# RADG-GPSRF-S02-V00.net
KiCad netlist of a schematic drawn in Altium Designer
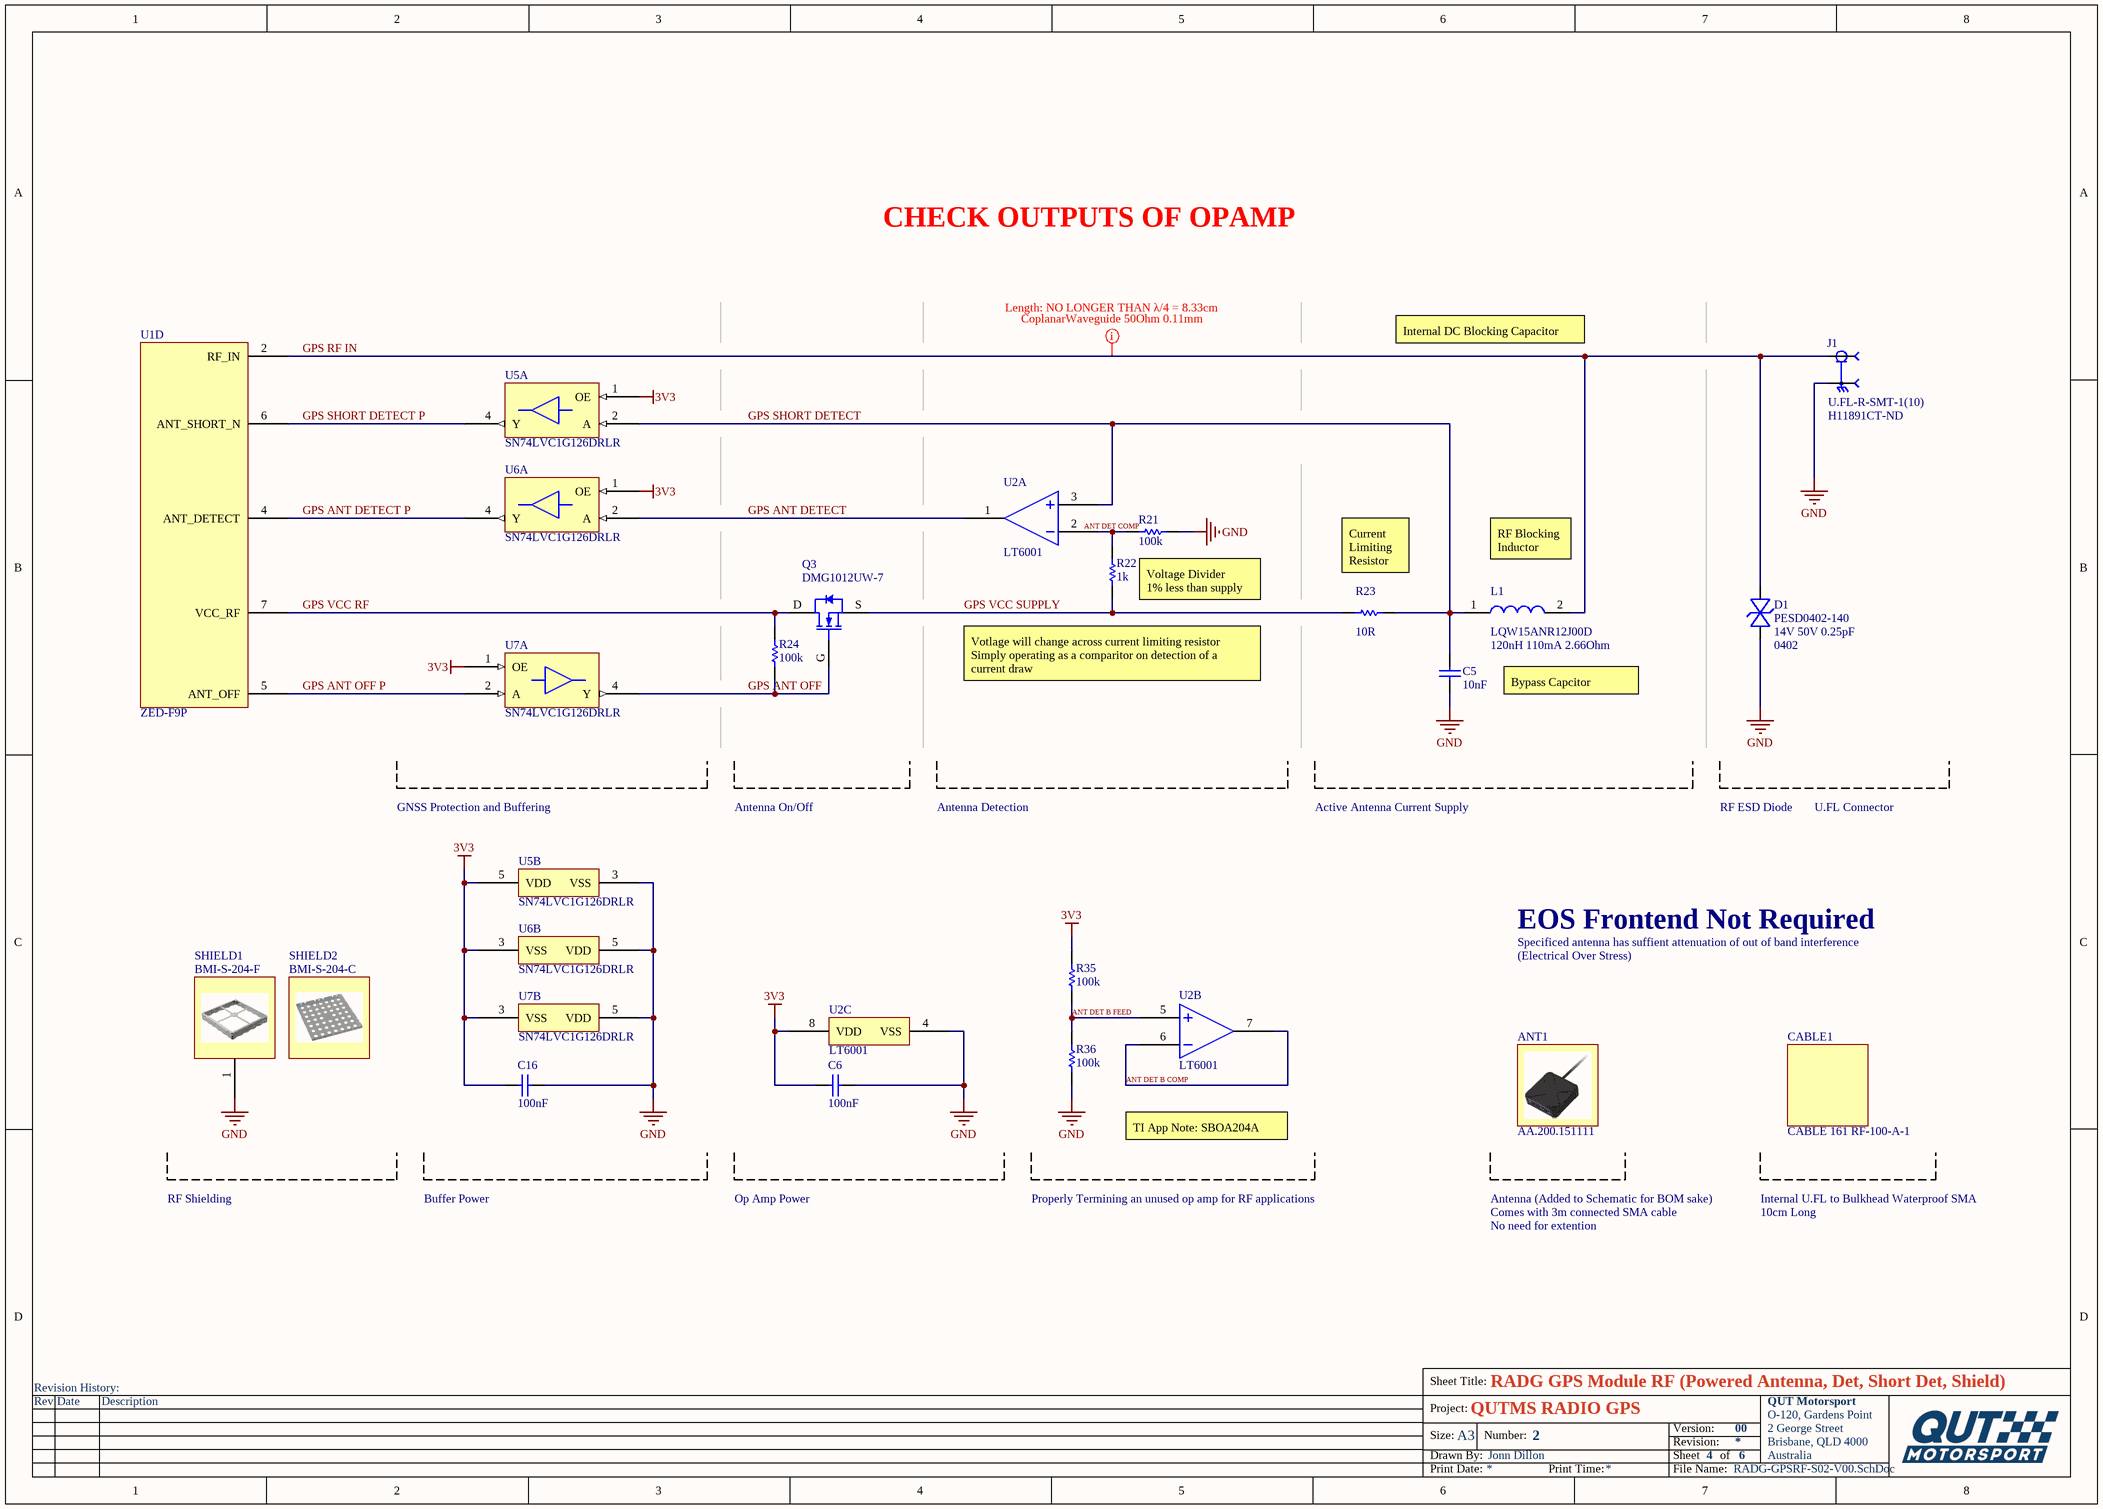
[diagram p0: RADG-GPSRF-S02-V00.SchDoc]

(export (version "E")
  (design (tool "Eeschema 10.0.6"))
  (components
    (comp (ref "ANT1")
      (value "AA.200.151111")
      (description "Antennas GNSS L1/L2/L5 External 1500mm RG-174 SMA(M) ST")
      (libsource (lib "QUTMS_RadioLibrary") (part "AA.200.151111"))
    )
    (comp (ref "C5")
      (value "10nF")
      (footprint "Cap_Ceramic_0603")
      (description "Capacitor, Ceramic, SMD, 10nF, 50V, 5%, X7R, 0603")
      (libsource (lib "StandardCapacitors") (part "10nF 50V 5% X7R 0603"))
    )
    (comp (ref "C6")
      (value "100nF")
      (footprint "Cap_Ceramic_0603")
      (description "Capacitor, Ceramic, SMD, 100nF, 50V, 5%, X7R, 0603")
      (libsource (lib "StandardCapacitors") (part "100nF 50V 5% X7R 0603"))
    )
    (comp (ref "C16")
      (value "100nF")
      (footprint "Cap_Ceramic_0603")
      (description "Capacitor, Ceramic, SMD, 100nF, 50V, 5%, X7R, 0603")
      (libsource (lib "StandardCapacitors") (part "100nF 50V 5% X7R 0603"))
    )
    (comp (ref "CABLE1")
      (value "CABLE 161 RF-100-A-1")
      (description "Cable Assembly Coaxial U.FL (UMCC), IPEX MHF1 to SMA Female to Female RG-178 3.937\" (100.00mm)")
      (libsource (lib "QUTMS_RadioLibrary") (part "CABLE 161 RF-100-A-1"))
    )
    (comp (ref "D1")
      (value "PESD0402-140")
      (footprint "FERRITEBEAD_0402")
      (description "40V Clamp Ipp Tvs Diode Surface Mount 0402")
      (libsource (lib "QUTMS_RadioLibrary") (part "PESD0402-140"))
    )
    (comp (ref "J1")
      (value "U.FL-R-SMT-1(10)")
      (footprint "U.FL-R-SMT HIROSE")
      (description "U.FL (UMCC) Connector Receptacle, Male Pin 50Ohm Surface Mount Solder,  H11891CT-ND")
      (libsource (lib "QUTMS_RadioLibrary") (part "U.FL-R-SMT-1(10)"))
    )
    (comp (ref "L1")
      (value "LQW15ANR12J00D")
      (footprint "FERRITEBEAD_0402")
      (description "120nH Unshielded Wirewound Inductor 110mA 2.66Ohm Max 0402 (1005 Metric)")
      (libsource (lib "QUTMS_RadioLibrary") (part "LQW15ANR12J00D"))
    )
    (comp (ref "Q3")
      (value "DMG1012UW-7")
      (footprint "SC-70")
      (description "N-Channel 20V 1A (Ta) 290mW (Ta) Surface Mount SOT-323")
      (libsource (lib "QUTMS_MOSFETLibrary") (part "DMG1012UW-7"))
    )
    (comp (ref "R21")
      (value "100k")
      (footprint "Res_ThinFilm_0603")
      (description "Resistor, SMD, 100k, 0.1W, 5%, 0603")
      (libsource (lib "StandardResistors") (part "100k 5%, 0603"))
    )
    (comp (ref "R22")
      (value "1k")
      (footprint "Res_ThinFilm_0603")
      (description "Resistor, SMD, 1k, 0.1W, 5%, 0603")
      (libsource (lib "StandardResistors") (part "1k 5% 0603"))
    )
    (comp (ref "R23")
      (value "10R")
      (footprint "Res_ThinFilm_0603")
      (description "Resistor, SMD, 10R, 0.1W, 5%, 0603")
      (libsource (lib "StandardResistors") (part "10R 5% 0603"))
    )
    (comp (ref "R24")
      (value "100k")
      (footprint "Res_ThinFilm_0603")
      (description "Resistor, SMD, 100k, 0.1W, 5%, 0603")
      (libsource (lib "StandardResistors") (part "100k 5%, 0603"))
    )
    (comp (ref "R35")
      (value "100k")
      (footprint "Res_ThinFilm_0603")
      (description "Resistor, SMD, 100k, 0.1W, 5%, 0603")
      (libsource (lib "StandardResistors") (part "100k 5%, 0603"))
    )
    (comp (ref "R36")
      (value "100k")
      (footprint "Res_ThinFilm_0603")
      (description "Resistor, SMD, 100k, 0.1W, 5%, 0603")
      (libsource (lib "StandardResistors") (part "100k 5%, 0603"))
    )
    (comp (ref "SHIELD1")
      (value "BMI-S-204-F")
      (footprint "BMI-S-204-F")
      (description "RF Shield Frame 1.260\" (32.00mm) X 1.260\" (32.00mm) Solder")
      (libsource (lib "QUTMS_RadioLibrary") (part "BMI-S-204-F"))
    )
    (comp (ref "SHIELD2")
      (value "BMI-S-204-C")
      (description "RF Shield Cover 1.344\" (34.14mm) X 1.468\" (37.29mm) Vent Holes in Pattern Snap Fit")
      (libsource (lib "QUTMS_RadioLibrary") (part "BMI-S-204-C"))
    )
    (comp (ref "U1")
      (value "ZED-F9P")
      (footprint "uBlox_ZED-F9P")
      (libsource (lib "QUTMS_RadioLibrary") (part "ZED-F9P"))
    )
    (comp (ref "U2")
      (value "LT6001")
      (footprint "MSOP-8")
      (description "General Purpose Amplifier 2 Circuit Rail-to-Rail 8-MSOP")
      (libsource (lib "") (part "LT6001_1"))
    )
    (comp (ref "U5")
      (value "SN74LVC1G126DRLR")
      (footprint "SOT-553")
      (description "Buffer, Non-Inverting 1 Element 1 Bit per Element 3-State Output SOT-5")
      (libsource (lib "QUTMS_IntegratedCircuitLibrary") (part "SN74LVC1G126DRLR"))
    )
    (comp (ref "U6")
      (value "SN74LVC1G126DRLR")
      (footprint "SOT-553")
      (description "Buffer, Non-Inverting 1 Element 1 Bit per Element 3-State Output SOT-5")
      (libsource (lib "QUTMS_IntegratedCircuitLibrary") (part "SN74LVC1G126DRLR"))
    )
    (comp (ref "U7")
      (value "SN74LVC1G126DRLR")
      (footprint "SOT-553")
      (description "Buffer, Non-Inverting 1 Element 1 Bit per Element 3-State Output SOT-5")
      (libsource (lib "QUTMS_IntegratedCircuitLibrary") (part "SN74LVC1G126DRLR"))
    )
  )
  (nets
    (net (code "1") (name "/ANT DET B COMP") (class "Default")
      (node (ref "U2") (pin "6") (pinfunction "IN2-_6") (pintype "passive"))
      (node (ref "U2") (pin "7") (pinfunction "OUT1_7") (pintype "passive"))
    )
    (net (code "2") (name "/ANT DET B FEED") (class "Default")
      (node (ref "R35") (pin "2") (pinfunction "2_2") (pintype "passive"))
      (node (ref "R36") (pin "1") (pinfunction "1_1") (pintype "passive"))
      (node (ref "U2") (pin "5") (pinfunction "IN2+_5") (pintype "passive"))
    )
    (net (code "3") (name "/ANT DET COMP") (class "Default")
      (node (ref "R21") (pin "2") (pinfunction "2_2") (pintype "passive"))
      (node (ref "R22") (pin "2") (pinfunction "2_2") (pintype "passive"))
      (node (ref "U2") (pin "2") (pinfunction "IN1-_2") (pintype "passive"))
    )
    (net (code "4") (name "/GPS ANT DETECT") (class "Default")
      (node (ref "U2") (pin "1") (pinfunction "OUT1_1") (pintype "passive"))
      (node (ref "U6") (pin "2") (pinfunction "A_2") (pintype "input"))
    )
    (net (code "5") (name "/GPS ANT DETECT P") (class "Default")
      (node (ref "U1") (pin "4") (pinfunction "ANT_DETECT_4") (pintype "passive"))
      (node (ref "U6") (pin "4") (pinfunction "Y_4") (pintype "output"))
    )
    (net (code "6") (name "/GPS ANT OFF") (class "Default")
      (node (ref "Q3") (pin "G") (pinfunction "G_G") (pintype "passive"))
      (node (ref "R24") (pin "1") (pinfunction "1_1") (pintype "passive"))
      (node (ref "U7") (pin "4") (pinfunction "Y_4") (pintype "output"))
    )
    (net (code "7") (name "/GPS ANT OFF P") (class "Default")
      (node (ref "U1") (pin "5") (pinfunction "ANT_OFF_5") (pintype "passive"))
      (node (ref "U7") (pin "2") (pinfunction "A_2") (pintype "input"))
    )
    (net (code "8") (name "/GPS RF IN") (class "Default")
      (node (ref "D1") (pin "2") (pinfunction "Cathode_2") (pintype "passive"))
      (node (ref "J1") (pin "1") (pinfunction "SIG_1") (pintype "passive"))
      (node (ref "L1") (pin "2") (pinfunction "2_2") (pintype "passive"))
      (node (ref "U1") (pin "2") (pinfunction "RF_IN_2") (pintype "passive"))
    )
    (net (code "9") (name "/GPS SHORT DETECT") (class "Default")
      (node (ref "C5") (pin "2") (pinfunction "2_2") (pintype "passive"))
      (node (ref "L1") (pin "1") (pinfunction "1_1") (pintype "passive"))
      (node (ref "R23") (pin "2") (pinfunction "2_2") (pintype "passive"))
      (node (ref "U2") (pin "3") (pinfunction "IN1+_3") (pintype "passive"))
      (node (ref "U5") (pin "2") (pinfunction "A_2") (pintype "input"))
    )
    (net (code "10") (name "/GPS SHORT DETECT P") (class "Default")
      (node (ref "U1") (pin "6") (pinfunction "ANT_SHORT_N_6") (pintype "passive"))
      (node (ref "U5") (pin "4") (pinfunction "Y_4") (pintype "output"))
    )
    (net (code "11") (name "/GPS VCC RF") (class "Default")
      (node (ref "Q3") (pin "D") (pinfunction "D_D") (pintype "passive"))
      (node (ref "R24") (pin "2") (pinfunction "2_2") (pintype "passive"))
      (node (ref "U1") (pin "7") (pinfunction "VCC_RF_7") (pintype "passive"))
    )
    (net (code "12") (name "/GPS VCC SUPPLY") (class "Default")
      (node (ref "Q3") (pin "S") (pinfunction "S_S") (pintype "passive"))
      (node (ref "R22") (pin "1") (pinfunction "1_1") (pintype "passive"))
      (node (ref "R23") (pin "1") (pinfunction "1_1") (pintype "passive"))
    )
    (net (code "13") (name "3V3") (class "Default")
      (node (ref "C16") (pin "1") (pinfunction "1_1") (pintype "passive"))
      (node (ref "C6") (pin "1") (pinfunction "1_1") (pintype "passive"))
      (node (ref "R35") (pin "1") (pinfunction "1_1") (pintype "passive"))
      (node (ref "U2") (pin "8") (pinfunction "VDD_8") (pintype "passive"))
      (node (ref "U5") (pin "1") (pinfunction "OE_1") (pintype "input"))
      (node (ref "U5") (pin "5") (pinfunction "VDD_5") (pintype "passive"))
      (node (ref "U6") (pin "1") (pinfunction "OE_1") (pintype "input"))
      (node (ref "U6") (pin "3") (pinfunction "VSS_3") (pintype "passive"))
      (node (ref "U7") (pin "1") (pinfunction "OE_1") (pintype "input"))
      (node (ref "U7") (pin "3") (pinfunction "VSS_3") (pintype "passive"))
    )
    (net (code "14") (name "GND") (class "Default")
      (node (ref "C16") (pin "2") (pinfunction "2_2") (pintype "passive"))
      (node (ref "C5") (pin "1") (pinfunction "1_1") (pintype "passive"))
      (node (ref "C6") (pin "2") (pinfunction "2_2") (pintype "passive"))
      (node (ref "D1") (pin "1") (pinfunction "Anode_1") (pintype "passive"))
      (node (ref "J1") (pin "2") (pinfunction "GND_2") (pintype "passive"))
      (node (ref "R21") (pin "1") (pinfunction "1_1") (pintype "passive"))
      (node (ref "R36") (pin "2") (pinfunction "2_2") (pintype "passive"))
      (node (ref "SHIELD1") (pin "1") (pinfunction "1_1") (pintype "passive"))
      (node (ref "U2") (pin "4") (pinfunction "VSS_4") (pintype "passive"))
      (node (ref "U5") (pin "3") (pinfunction "VSS_3") (pintype "passive"))
      (node (ref "U6") (pin "5") (pinfunction "VDD_5") (pintype "passive"))
      (node (ref "U7") (pin "5") (pinfunction "VDD_5") (pintype "passive"))
    )
  )
)
